# 3V3_Buck_Regulator.net
KiCad netlist of a schematic drawn in Altium Designer
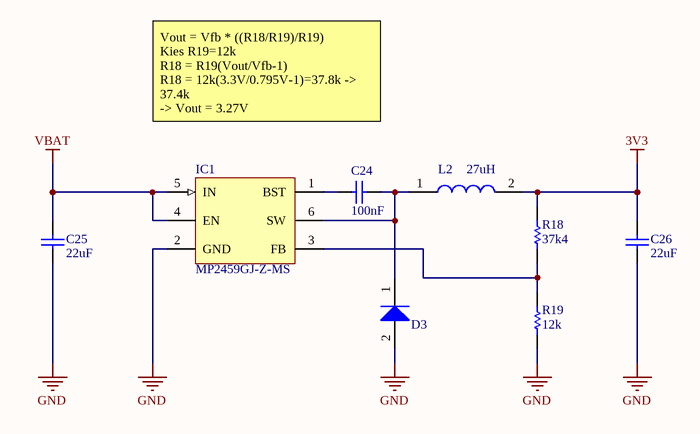
[diagram p0: 3V3_Buck_Regulator.SchDoc]

(export (version "E")
  (design (tool "Eeschema 10.0.6"))
  (components
    (comp (ref "C24")
      (value "100nF")
      (footprint "Wurth 0603 capacitor")
      (fields (field (name "Comment") "Generic Capacitor 100nF 0603"))
      (libsource (lib "Passives") (part "Generic Capacitor 100nF 0603"))
    )
    (comp (ref "C25")
      (value "22uF")
      (footprint "Wurth 0805 capacitor")
      (fields (field (name "Comment") "Generic Capacitor 22uF 0805"))
      (libsource (lib "Passives") (part "Generic Capacitor 22uF 0805"))
    )
    (comp (ref "C26")
      (value "22uF")
      (footprint "Wurth 0805 capacitor")
      (fields (field (name "Comment") "Generic Capacitor 22uF 0805"))
      (libsource (lib "Passives") (part "Generic Capacitor 22uF 0805"))
    )
    (comp (ref "D3")
      (value "Diode RF071MM2STFTR")
      (footprint "Rohm SOD-123")
      (libsource (lib "Passives") (part "Diode RF071MM2STFTR"))
    )
    (comp (ref "IC1")
      (value "MP2459GJ-Z-MS")
      (footprint "Texas InstrumentsSOT95P280X110-6N")
      (description "Buck Converter 4.5V-60V 600mA")
      (libsource (lib "Buck_Converter") (part "MSKSEMI MP2459GJ-Z-MS"))
    )
    (comp (ref "L2")
      (value "27uH")
      (footprint "3L COILS 5.2X5.8MM")
      (fields (field (name "MANUFACTURER") "3L Coils") (field (name "Comment") "COILS SMTDR54-270M"))
      (libsource (lib "Passives") (part "3L COILS SMTDR54-270M inductor"))
    )
    (comp (ref "R18")
      (value "37k4")
      (footprint "Wurth 0603 Resistor")
      (fields (field (name "Comment") "Generic Resistor 37k4 0603"))
      (libsource (lib "Passives") (part "Generic Resistor 37k4 0603"))
    )
    (comp (ref "R19")
      (value "12k")
      (footprint "Wurth 0603 Resistor")
      (fields (field (name "Comment") "Generic Resistor 12k 0603"))
      (libsource (lib "Passives") (part "Generic Resistor 12k 0603"))
    )
  )
  (nets
    (net (code "1") (name "3V3") (class "Default")
      (node (ref "C26") (pin "2") (pinfunction "2_2") (pintype "passive"))
      (node (ref "L2") (pin "2") (pinfunction "2_2") (pintype "passive"))
      (node (ref "R18") (pin "2") (pinfunction "2_2") (pintype "passive"))
    )
    (net (code "2") (name "GND") (class "Default")
      (node (ref "C25") (pin "1") (pinfunction "1_1") (pintype "passive"))
      (node (ref "C26") (pin "1") (pinfunction "1_1") (pintype "passive"))
      (node (ref "D3") (pin "2") (pinfunction "A_2") (pintype "passive"))
      (node (ref "IC1") (pin "2") (pinfunction "GND_2") (pintype "power_in"))
      (node (ref "R19") (pin "1") (pinfunction "1_1") (pintype "passive"))
    )
    (net (code "3") (name "Net-(D3-K)") (class "Default")
      (node (ref "C24") (pin "2") (pinfunction "2_2") (pintype "passive"))
      (node (ref "D3") (pin "1") (pinfunction "K_1") (pintype "passive"))
      (node (ref "IC1") (pin "6") (pinfunction "SW_6") (pintype "passive"))
      (node (ref "L2") (pin "1") (pinfunction "1_1") (pintype "passive"))
    )
    (net (code "4") (name "Net-(IC1-BST)") (class "Default")
      (node (ref "C24") (pin "1") (pinfunction "1_1") (pintype "passive"))
      (node (ref "IC1") (pin "1") (pinfunction "BST_1") (pintype "passive"))
    )
    (net (code "5") (name "Net-(IC1-FB)") (class "Default")
      (node (ref "IC1") (pin "3") (pinfunction "FB_3") (pintype "passive"))
      (node (ref "R18") (pin "1") (pinfunction "1_1") (pintype "passive"))
      (node (ref "R19") (pin "2") (pinfunction "2_2") (pintype "passive"))
    )
    (net (code "6") (name "VBAT") (class "Default")
      (node (ref "C25") (pin "2") (pinfunction "2_2") (pintype "passive"))
      (node (ref "IC1") (pin "4") (pinfunction "EN_4") (pintype "passive"))
      (node (ref "IC1") (pin "5") (pinfunction "IN_5") (pintype "input"))
    )
  )
)
